# VDS_botboard_beaglebone_revA.net
KiCad netlist of a schematic drawn in EAGLE
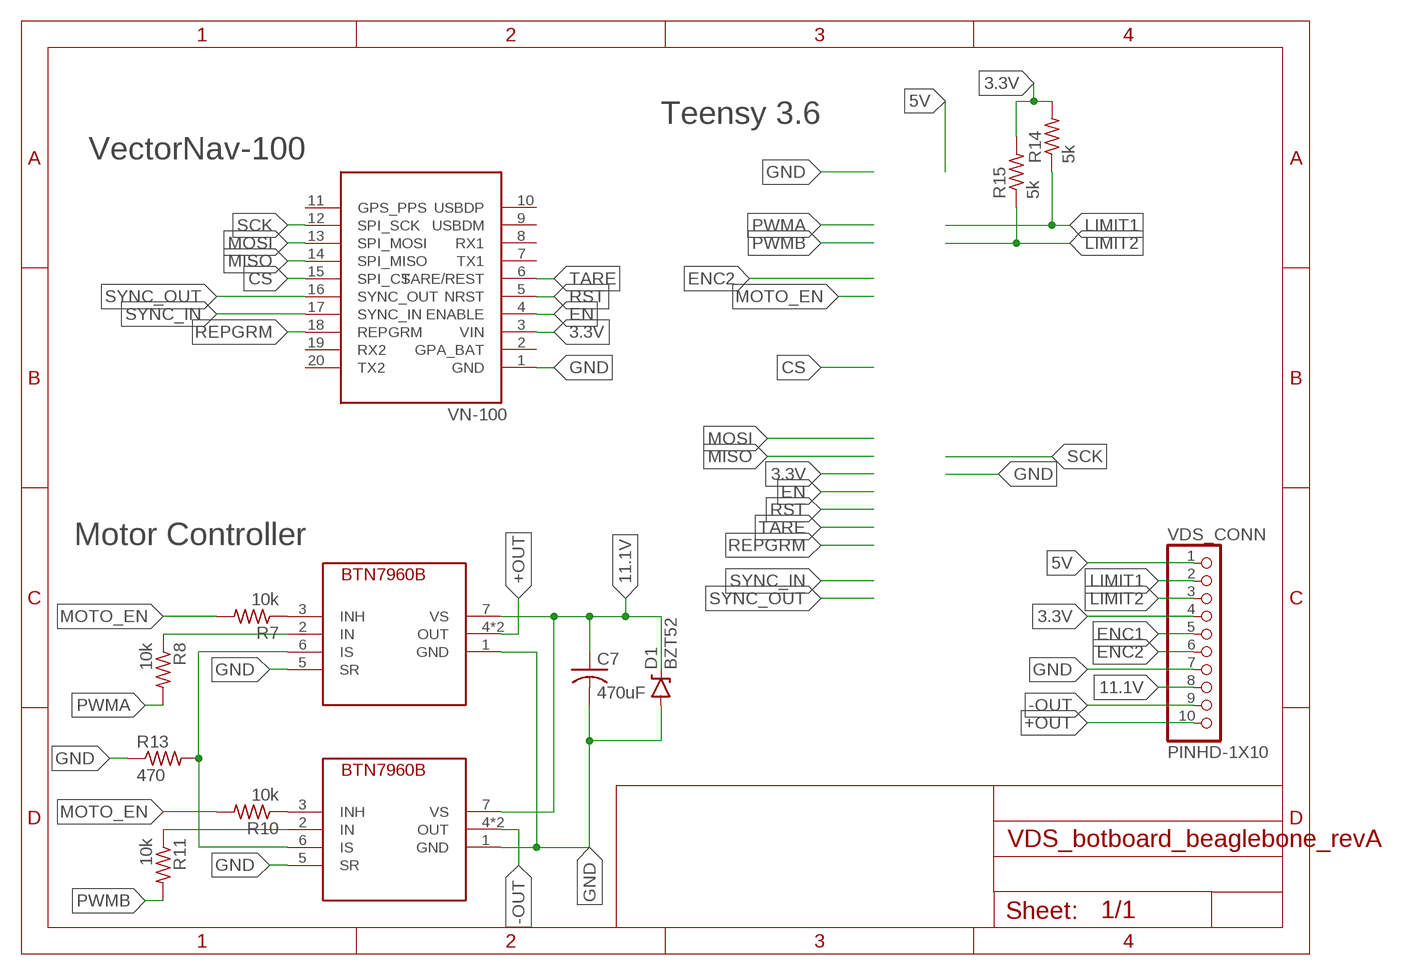
[diagram p0: schematic, sheet 1]

(export (version "E")
  (design (tool "Eeschema 10.0.6"))
  (components
    (comp (ref "C7")
      (value "470uF")
      (footprint "eagle-import:C050-024X044")
      (libsource (lib "eagle-import") (part "C-US050-024X044"))
    )
    (comp (ref "D1")
      (value "BZT52")
      (footprint "eagle-import:DIODE-BZT52")
      (libsource (lib "eagle-import") (part "DIODE-ZENER"))
    )
    (comp (ref "R7")
      (value "10k")
      (footprint "eagle-import:0204_5")
      (libsource (lib "eagle-import") (part "R-US_0204/5"))
    )
    (comp (ref "R8")
      (value "10k")
      (footprint "eagle-import:0204_5")
      (libsource (lib "eagle-import") (part "R-US_0204/5"))
    )
    (comp (ref "R10")
      (value "10k")
      (footprint "eagle-import:0204_5")
      (libsource (lib "eagle-import") (part "R-US_0204/5"))
    )
    (comp (ref "R11")
      (value "10k")
      (footprint "eagle-import:0204_5")
      (libsource (lib "eagle-import") (part "R-US_0204/5"))
    )
    (comp (ref "R13")
      (value "470")
      (footprint "eagle-import:0204_5")
      (libsource (lib "eagle-import") (part "R-US_0204/5"))
    )
    (comp (ref "R14")
      (value "5k")
      (footprint "eagle-import:0204_5")
      (libsource (lib "eagle-import") (part "R-US_0204/5"))
    )
    (comp (ref "R15")
      (value "5k")
      (footprint "eagle-import:0204_5")
      (libsource (lib "eagle-import") (part "R-US_0204/5"))
    )
    (comp (ref "U1")
      (value "INF-PG-TO263-7-1_L_1_BTN7960B")
      (footprint "eagle-import:INF-PG-TO263-7-1_L_1PRIMARY")
      (libsource (lib "eagle-import") (part "INF-PG-TO263-7-1_L_1_BTN7960B"))
    )
    (comp (ref "U2")
      (value "INF-PG-TO263-7-1_L_1_BTN7960B")
      (footprint "eagle-import:INF-PG-TO263-7-1_L_1PRIMARY")
      (libsource (lib "eagle-import") (part "INF-PG-TO263-7-1_L_1_BTN7960B"))
    )
    (comp (ref "VDS_CONN")
      (value "PINHD-1X10")
      (footprint "eagle-import:1X10-BIG")
      (libsource (lib "eagle-import") (part "PINHD-1X10"))
    )
    (comp (ref "VN1")
      (value "VECTORNAV-100")
      (footprint "eagle-import:VN-100")
      (libsource (lib "eagle-import") (part "VECTORNAV-100"))
    )
  )
  (nets
    (net (code "1") (name "+OUT") (class "Default")
      (node (ref "U1") (pin "4") (pinfunction "OUT_4") (pintype "bidirectional"))
      (node (ref "U1") (pin "8") (pinfunction "OUT_8") (pintype "bidirectional"))
      (node (ref "VDS_CONN") (pin "10") (pinfunction "10_10") (pintype "passive"))
    )
    (net (code "2") (name "-OUT") (class "Default")
      (node (ref "U2") (pin "4") (pinfunction "OUT_4") (pintype "bidirectional"))
      (node (ref "U2") (pin "8") (pinfunction "OUT_8") (pintype "bidirectional"))
      (node (ref "VDS_CONN") (pin "9") (pinfunction "9_9") (pintype "passive"))
    )
    (net (code "3") (name "3.3V") (class "Default")
      (node (ref "R14") (pin "2") (pinfunction "2_2") (pintype "passive"))
      (node (ref "R15") (pin "2") (pinfunction "2_2") (pintype "passive"))
      (node (ref "VDS_CONN") (pin "4") (pinfunction "4_4") (pintype "passive"))
      (node (ref "VN1") (pin "3") (pinfunction "VIN_3") (pintype "bidirectional"))
    )
    (net (code "4") (name "5V") (class "Default")
      (node (ref "VDS_CONN") (pin "1") (pinfunction "1_1") (pintype "passive"))
    )
    (net (code "5") (name "11.1V") (class "Default")
      (node (ref "C7") (pin "1") (pinfunction "1_1") (pintype "passive"))
      (node (ref "D1") (pin "C") (pinfunction "C_C") (pintype "passive"))
      (node (ref "U1") (pin "7") (pinfunction "VS_7") (pintype "bidirectional"))
      (node (ref "U2") (pin "7") (pinfunction "VS_7") (pintype "bidirectional"))
      (node (ref "VDS_CONN") (pin "8") (pinfunction "8_8") (pintype "passive"))
    )
    (net (code "6") (name "CS") (class "Default")
      (node (ref "VN1") (pin "15") (pinfunction "SPI_CS_15") (pintype "bidirectional"))
    )
    (net (code "7") (name "EN") (class "Default")
      (node (ref "VN1") (pin "4") (pinfunction "ENABLE_4") (pintype "bidirectional"))
    )
    (net (code "8") (name "ENC1") (class "Default")
      (node (ref "VDS_CONN") (pin "5") (pinfunction "5_5") (pintype "passive"))
    )
    (net (code "9") (name "ENC2") (class "Default")
      (node (ref "VDS_CONN") (pin "6") (pinfunction "6_6") (pintype "passive"))
    )
    (net (code "10") (name "GND") (class "Default")
      (node (ref "C7") (pin "2") (pinfunction "2_2") (pintype "passive"))
      (node (ref "D1") (pin "A") (pinfunction "A_A") (pintype "passive"))
      (node (ref "R13") (pin "1") (pinfunction "1_1") (pintype "passive"))
      (node (ref "U1") (pin "1") (pinfunction "GND_1") (pintype "bidirectional"))
      (node (ref "U1") (pin "5") (pinfunction "SR_5") (pintype "bidirectional"))
      (node (ref "U2") (pin "1") (pinfunction "GND_1") (pintype "bidirectional"))
      (node (ref "U2") (pin "5") (pinfunction "SR_5") (pintype "bidirectional"))
      (node (ref "VDS_CONN") (pin "7") (pinfunction "7_7") (pintype "passive"))
      (node (ref "VN1") (pin "1") (pinfunction "GND_1") (pintype "bidirectional"))
    )
    (net (code "11") (name "LIMIT1") (class "Default")
      (node (ref "R14") (pin "1") (pinfunction "1_1") (pintype "passive"))
      (node (ref "VDS_CONN") (pin "2") (pinfunction "2_2") (pintype "passive"))
    )
    (net (code "12") (name "LIMIT2") (class "Default")
      (node (ref "R15") (pin "1") (pinfunction "1_1") (pintype "passive"))
      (node (ref "VDS_CONN") (pin "3") (pinfunction "3_3") (pintype "passive"))
    )
    (net (code "13") (name "MISO") (class "Default")
      (node (ref "VN1") (pin "14") (pinfunction "SPI_MISO_14") (pintype "bidirectional"))
    )
    (net (code "14") (name "MOSI") (class "Default")
      (node (ref "VN1") (pin "13") (pinfunction "SPI_MOSI_13") (pintype "bidirectional"))
    )
    (net (code "15") (name "MOTO_EN") (class "Default")
      (node (ref "R10") (pin "2") (pinfunction "2_2") (pintype "passive"))
      (node (ref "R7") (pin "2") (pinfunction "2_2") (pintype "passive"))
    )
    (net (code "16") (name "Net-(U1-IN)") (class "Default")
      (node (ref "R8") (pin "1") (pinfunction "1_1") (pintype "passive"))
      (node (ref "U1") (pin "2") (pinfunction "IN_2") (pintype "bidirectional"))
    )
    (net (code "17") (name "Net-(U1-INH)") (class "Default")
      (node (ref "R7") (pin "1") (pinfunction "1_1") (pintype "passive"))
      (node (ref "U1") (pin "3") (pinfunction "INH_3") (pintype "bidirectional"))
    )
    (net (code "18") (name "Net-(U1-IS)") (class "Default")
      (node (ref "R13") (pin "2") (pinfunction "2_2") (pintype "passive"))
      (node (ref "U1") (pin "6") (pinfunction "IS_6") (pintype "bidirectional"))
      (node (ref "U2") (pin "6") (pinfunction "IS_6") (pintype "bidirectional"))
    )
    (net (code "19") (name "Net-(U2-IN)") (class "Default")
      (node (ref "R11") (pin "1") (pinfunction "1_1") (pintype "passive"))
      (node (ref "U2") (pin "2") (pinfunction "IN_2") (pintype "bidirectional"))
    )
    (net (code "20") (name "Net-(U2-INH)") (class "Default")
      (node (ref "R10") (pin "1") (pinfunction "1_1") (pintype "passive"))
      (node (ref "U2") (pin "3") (pinfunction "INH_3") (pintype "bidirectional"))
    )
    (net (code "21") (name "PWMA") (class "Default")
      (node (ref "R8") (pin "2") (pinfunction "2_2") (pintype "passive"))
    )
    (net (code "22") (name "PWMB") (class "Default")
      (node (ref "R11") (pin "2") (pinfunction "2_2") (pintype "passive"))
    )
    (net (code "23") (name "REPGRM") (class "Default")
      (node (ref "VN1") (pin "18") (pinfunction "REPGRM_18") (pintype "bidirectional"))
    )
    (net (code "24") (name "RST") (class "Default")
      (node (ref "VN1") (pin "5") (pinfunction "NRST_5") (pintype "bidirectional"))
    )
    (net (code "25") (name "SCK") (class "Default")
      (node (ref "VN1") (pin "12") (pinfunction "SPI_SCK_12") (pintype "bidirectional"))
    )
    (net (code "26") (name "SYNC_IN") (class "Default")
      (node (ref "VN1") (pin "17") (pinfunction "SYNC_IN_17") (pintype "bidirectional"))
    )
    (net (code "27") (name "SYNC_OUT") (class "Default")
      (node (ref "VN1") (pin "16") (pinfunction "SYNC_OUT_16") (pintype "bidirectional"))
    )
    (net (code "28") (name "TARE") (class "Default")
      (node (ref "VN1") (pin "6") (pinfunction "TARE/REST_6") (pintype "bidirectional"))
    )
    (net (code "29") (name "unconnected-(VN1-GPA_BAT-Pad2)") (class "Default")
      (node (ref "VN1") (pin "2") (pinfunction "GPA_BAT_2") (pintype "bidirectional"))
    )
    (net (code "30") (name "unconnected-(VN1-GPS_PPS-Pad11)") (class "Default")
      (node (ref "VN1") (pin "11") (pinfunction "GPS_PPS_11") (pintype "bidirectional"))
    )
    (net (code "31") (name "unconnected-(VN1-RX1-Pad8)") (class "Default")
      (node (ref "VN1") (pin "8") (pinfunction "RX1_8") (pintype "bidirectional"))
    )
    (net (code "32") (name "unconnected-(VN1-RX2-Pad19)") (class "Default")
      (node (ref "VN1") (pin "19") (pinfunction "RX2_19") (pintype "bidirectional"))
    )
    (net (code "33") (name "unconnected-(VN1-TX1-Pad7)") (class "Default")
      (node (ref "VN1") (pin "7") (pinfunction "TX1_7") (pintype "bidirectional"))
    )
    (net (code "34") (name "unconnected-(VN1-TX2-Pad20)") (class "Default")
      (node (ref "VN1") (pin "20") (pinfunction "TX2_20") (pintype "bidirectional"))
    )
    (net (code "35") (name "unconnected-(VN1-USBDM-Pad9)") (class "Default")
      (node (ref "VN1") (pin "9") (pinfunction "USBDM_9") (pintype "bidirectional"))
    )
    (net (code "36") (name "unconnected-(VN1-USBDP-Pad10)") (class "Default")
      (node (ref "VN1") (pin "10") (pinfunction "USBDP_10") (pintype "bidirectional"))
    )
  )
)
